# COMPOSITE_SCH.net
KiCad netlist of a schematic drawn in EAGLE
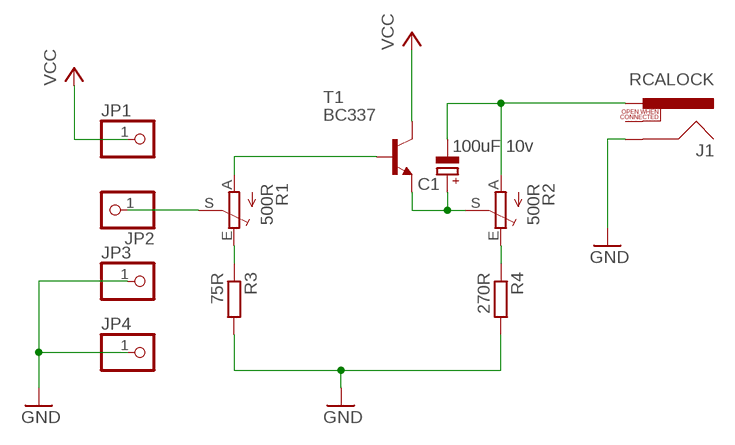
[diagram p0: schematic, sheet 1]

(export (version "E")
  (design (tool "Eeschema 10.0.6"))
  (components
    (comp (ref "C1")
      (value "100uF 10v")
      (footprint "eagle-import:E2,5-6E")
      (libsource (lib "eagle-import") (part "CPOL-EUE2,5-6E"))
    )
    (comp (ref "J1")
      (value "RCALOCK")
      (footprint "eagle-import:RCA_LOCK")
      (libsource (lib "eagle-import") (part "RCALOCK"))
    )
    (comp (ref "JP1")
      (value "PINHD-1X1")
      (footprint "eagle-import:1X01")
      (libsource (lib "eagle-import") (part "PINHD-1X1"))
    )
    (comp (ref "JP2")
      (value "PINHD-1X1")
      (footprint "eagle-import:1X01")
      (libsource (lib "eagle-import") (part "PINHD-1X1"))
    )
    (comp (ref "JP3")
      (value "PINHD-1X1")
      (footprint "eagle-import:1X01")
      (libsource (lib "eagle-import") (part "PINHD-1X1"))
    )
    (comp (ref "JP4")
      (value "PINHD-1X1")
      (footprint "eagle-import:1X01")
      (libsource (lib "eagle-import") (part "PINHD-1X1"))
    )
    (comp (ref "R1")
      (value "500R")
      (footprint "eagle-import:CA6V")
      (libsource (lib "eagle-import") (part "TRIM_EU-CA6V"))
    )
    (comp (ref "R2")
      (value "500R")
      (footprint "eagle-import:CA6V")
      (libsource (lib "eagle-import") (part "TRIM_EU-CA6V"))
    )
    (comp (ref "R3")
      (value "75R")
      (footprint "eagle-import:0207_10")
      (libsource (lib "eagle-import") (part "R-EU_0207/10"))
    )
    (comp (ref "R4")
      (value "270R")
      (footprint "eagle-import:0207_10")
      (libsource (lib "eagle-import") (part "R-EU_0207/10"))
    )
    (comp (ref "T1")
      (value "BC337")
      (footprint "eagle-import:TO92")
      (libsource (lib "eagle-import") (part "BC337"))
    )
  )
  (nets
    (net (code "1") (name "GND") (class "Default")
      (node (ref "J1") (pin "SHELL") (pinfunction "SHELL_SHELL") (pintype "bidirectional"))
      (node (ref "JP3") (pin "1") (pinfunction "1_1") (pintype "passive"))
      (node (ref "JP4") (pin "1") (pinfunction "1_1") (pintype "passive"))
      (node (ref "R3") (pin "2") (pinfunction "2_2") (pintype "passive"))
      (node (ref "R4") (pin "2") (pinfunction "2_2") (pintype "passive"))
    )
    (net (code "2") (name "Net-(C1-Pad-)") (class "Default")
      (node (ref "C1") (pin "-") (pinfunction "-_-") (pintype "passive"))
      (node (ref "J1") (pin "PIN") (pinfunction "PIN_PIN") (pintype "bidirectional"))
      (node (ref "R2") (pin "A") (pinfunction "A_A") (pintype "passive"))
    )
    (net (code "3") (name "Net-(JP2-Pad1)") (class "Default")
      (node (ref "JP2") (pin "1") (pinfunction "1_1") (pintype "passive"))
      (node (ref "R1") (pin "S") (pinfunction "S_S") (pintype "passive"))
    )
    (net (code "4") (name "Net-(R1-PadE)") (class "Default")
      (node (ref "R1") (pin "E") (pinfunction "E_E") (pintype "passive"))
      (node (ref "R3") (pin "1") (pinfunction "1_1") (pintype "passive"))
    )
    (net (code "5") (name "Net-(R2-PadE)") (class "Default")
      (node (ref "R2") (pin "E") (pinfunction "E_E") (pintype "passive"))
      (node (ref "R4") (pin "1") (pinfunction "1_1") (pintype "passive"))
    )
    (net (code "6") (name "Net-(T1-B)") (class "Default")
      (node (ref "R1") (pin "A") (pinfunction "A_A") (pintype "passive"))
      (node (ref "T1") (pin "2") (pinfunction "B_2") (pintype "passive"))
    )
    (net (code "7") (name "Net-(T1-E)") (class "Default")
      (node (ref "C1") (pin "+") (pinfunction "+_+") (pintype "passive"))
      (node (ref "R2") (pin "S") (pinfunction "S_S") (pintype "passive"))
      (node (ref "T1") (pin "1") (pinfunction "E_1") (pintype "passive"))
    )
    (net (code "8") (name "VCC") (class "Default")
      (node (ref "JP1") (pin "1") (pinfunction "1_1") (pintype "passive"))
      (node (ref "T1") (pin "3") (pinfunction "C_3") (pintype "passive"))
    )
    (net (code "9") (name "unconnected-(J1-PadSWITCH)") (class "Default")
      (node (ref "J1") (pin "SWITCH") (pinfunction "SWITCH_SWITCH") (pintype "bidirectional"))
    )
  )
)
